# Knobber_Topsheet.net
KiCad netlist of a schematic drawn in Altium Designer
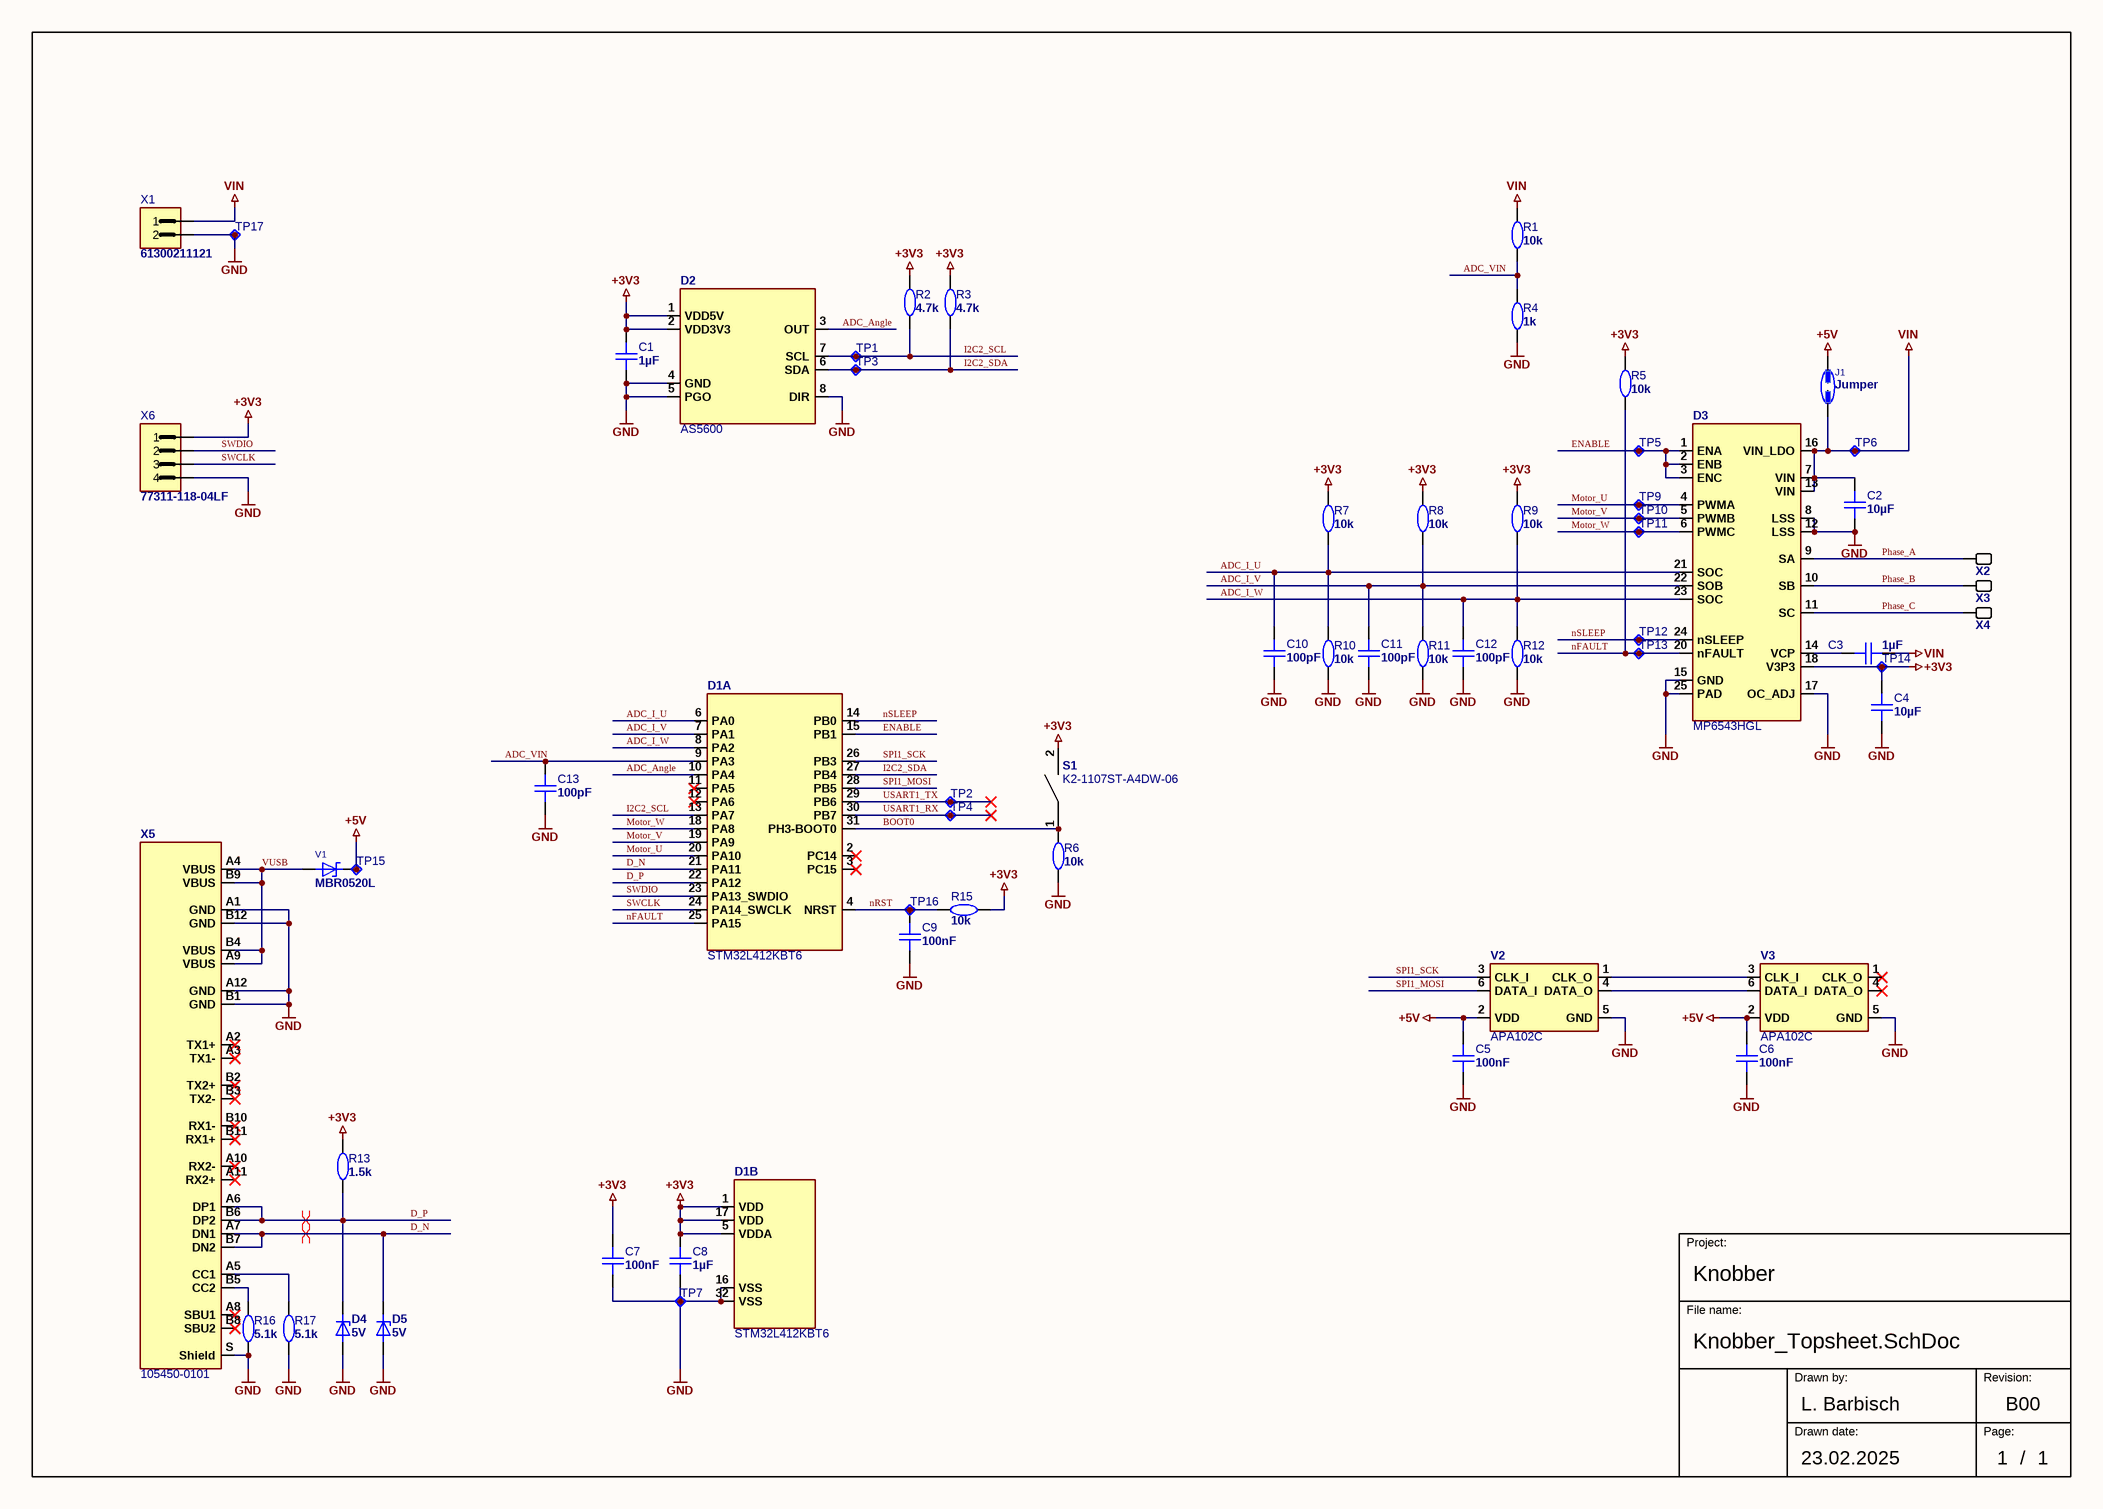
[diagram p0: Knobber_Topsheet.SchDoc]

(export (version "E")
  (design (tool "Eeschema 10.0.6"))
  (components
    (comp (ref "C1")
      (value "1µF")
      (footprint "C-0603_1608_095_L_RF")
      (description "Cap Cer SMD 1u 16V 10% 0603 X7R")
      (fields
        (field (name "MANUFACTURER PART NUMBER") "0603YC105KAT2A")
        (field (name "MANUFACTURER") "AVX")
        (field (name "USER") "epph")
      )
      (libsource (lib "GPV Switzerland SA") (part "CAP"))
    )
    (comp (ref "C2")
      (value "10µF")
      (footprint "C-1210_3225_230_L_RF")
      (description "CAP CER 10uF 50V X7S 1210")
      (fields
        (field (name "MANUFACTURER") "TDK")
        (field (name "MANUFACTURER PART NUMBER") "C3225X7S1H106K250AE")
        (field (name "USER") "zupa")
      )
      (libsource (lib "GPV Switzerland SA") (part "CAP"))
    )
    (comp (ref "C3")
      (value "1µF")
      (footprint "C-0603_1608_095_L_RF")
      (description "Cap Cer SMD 1u 16V 10% 0603 X7R")
      (fields
        (field (name "MANUFACTURER PART NUMBER") "0603YC105KAT2A")
        (field (name "MANUFACTURER") "AVX")
        (field (name "USER") "epph")
      )
      (libsource (lib "GPV Switzerland SA") (part "CAP"))
    )
    (comp (ref "C4")
      (value "10µF")
      (footprint "C-0805_2012_145_L_RF")
      (description "Cap Cer SMD 10u 16V 10% 0805 X5R")
      (fields
        (field (name "MANUFACTURER PART NUMBER") "0805YD106KAT2A")
        (field (name "MANUFACTURER") "AVX")
        (field (name "USER") "zupa")
      )
      (libsource (lib "GPV Switzerland SA") (part "CAP"))
    )
    (comp (ref "C5")
      (value "100nF")
      (footprint "C-0603_1608_095_L_RF")
      (description "Cap Cer SMD 100n 100V 10% 0603 X7R")
      (fields
        (field (name "MANUFACTURER PART NUMBER") "GRM188R72A104KA35")
        (field (name "MANUFACTURER") "MURATA")
        (field (name "USER") "zupa")
      )
      (libsource (lib "GPV Switzerland SA") (part "CAP"))
    )
    (comp (ref "C6")
      (value "100nF")
      (footprint "C-0603_1608_095_L_RF")
      (description "Cap Cer SMD 100n 100V 10% 0603 X7R")
      (fields
        (field (name "MANUFACTURER PART NUMBER") "GRM188R72A104KA35")
        (field (name "MANUFACTURER") "MURATA")
        (field (name "USER") "zupa")
      )
      (libsource (lib "GPV Switzerland SA") (part "CAP"))
    )
    (comp (ref "C7")
      (value "100nF")
      (footprint "C-0603_1608_095_L_RF")
      (description "Cap Cer SMD 100n 100V 10% 0603 X7R")
      (fields
        (field (name "MANUFACTURER PART NUMBER") "GRM188R72A104KA35")
        (field (name "MANUFACTURER") "MURATA")
        (field (name "USER") "zupa")
      )
      (libsource (lib "GPV Switzerland SA") (part "CAP"))
    )
    (comp (ref "C8")
      (value "1µF")
      (footprint "C-0603_1608_095_L_RF")
      (description "Cap Cer SMD 1u 16V 10% 0603 X7R")
      (fields
        (field (name "MANUFACTURER PART NUMBER") "0603YC105KAT2A")
        (field (name "MANUFACTURER") "AVX")
        (field (name "USER") "epph")
      )
      (libsource (lib "GPV Switzerland SA") (part "CAP"))
    )
    (comp (ref "C9")
      (value "100nF")
      (footprint "C-0603_1608_095_L_RF")
      (description "Cap Cer SMD 100n 100V 10% 0603 X7R")
      (fields
        (field (name "MANUFACTURER PART NUMBER") "GRM188R72A104KA35")
        (field (name "MANUFACTURER") "MURATA")
        (field (name "USER") "zupa")
      )
      (libsource (lib "GPV Switzerland SA") (part "CAP"))
    )
    (comp (ref "C10")
      (value "100pF")
      (footprint "C-0603_1608_095_L_RF")
      (description "Cap Cer SMD 100p 50V 5% 0603 C0G")
      (fields
        (field (name "MANUFACTURER PART NUMBER") "CC0603J*NPO9BN101")
        (field (name "MANUFACTURER") "YAGEO")
        (field (name "USER") "zupa")
      )
      (libsource (lib "GPV Switzerland SA") (part "CAP"))
    )
    (comp (ref "C11")
      (value "100pF")
      (footprint "C-0603_1608_095_L_RF")
      (description "Cap Cer SMD 100p 50V 5% 0603 C0G")
      (fields
        (field (name "MANUFACTURER PART NUMBER") "CC0603J*NPO9BN101")
        (field (name "MANUFACTURER") "YAGEO")
        (field (name "USER") "zupa")
      )
      (libsource (lib "GPV Switzerland SA") (part "CAP"))
    )
    (comp (ref "C12")
      (value "100pF")
      (footprint "C-0603_1608_095_L_RF")
      (description "Cap Cer SMD 100p 50V 5% 0603 C0G")
      (fields
        (field (name "MANUFACTURER PART NUMBER") "CC0603J*NPO9BN101")
        (field (name "MANUFACTURER") "YAGEO")
        (field (name "USER") "zupa")
      )
      (libsource (lib "GPV Switzerland SA") (part "CAP"))
    )
    (comp (ref "C13")
      (value "100pF")
      (footprint "C-0603_1608_095_L_RF")
      (description "Cap Cer SMD 100p 50V 5% 0603 C0G")
      (fields
        (field (name "MANUFACTURER PART NUMBER") "CC0603J*NPO9BN101")
        (field (name "MANUFACTURER") "YAGEO")
        (field (name "USER") "zupa")
      )
      (libsource (lib "GPV Switzerland SA") (part "CAP"))
    )
    (comp (ref "D1")
      (value "STM32L412KBT6")
      (footprint "LQFP32_N_RF")
      (description "IC MCU STM32")
      (fields (field (name "MANUFACTURER") "STM"))
      (libsource (lib "Global Library") (part "STM32L412KBT6"))
    )
    (comp (ref "D2")
      (value "AS5600")
      (footprint "SOIC8_N_RF")
      (description "IC Sensor Rotation Magnet 12bit")
      (fields (field (name "MANUFACTURER") "AMS"))
      (libsource (lib "Global Library") (part "AS5600"))
    )
    (comp (ref "D3")
      (value "MP6543HGL")
      (footprint "QFN24_5x7_N_RF")
      (description "Motor Driver 3-Phase 3-22V 2A")
      (fields
        (field (name "MANUFACTURER") "Monolithic Power Systems")
        (field (name "MANUFACTURER PART NUMBER") "MP6543HGL-A-P")
      )
      (libsource (lib "Global Library") (part "MP6543HGL-A-P"))
    )
    (comp (ref "D4")
      (value "5V")
      (footprint "SOD-923_N_RF")
      (description "Diode ESD 5V")
      (fields
        (field (name "MANUFACTURER") "Onsemi")
        (field (name "MANUFACTURER PART NUMBER") "ESD9101P2T5G")
        (field (name "PART_VALIDATED") "Yes ¦ No")
        (field (name "FOOTPRINT_VALIDATED") "Yes ¦ No")
      )
      (libsource (lib "Global Library") (part "ESD9101"))
    )
    (comp (ref "D5")
      (value "5V")
      (footprint "SOD-923_N_RF")
      (description "Diode ESD 5V")
      (fields
        (field (name "MANUFACTURER") "Onsemi")
        (field (name "MANUFACTURER PART NUMBER") "ESD9101P2T5G")
        (field (name "PART_VALIDATED") "Yes ¦ No")
        (field (name "FOOTPRINT_VALIDATED") "Yes ¦ No")
      )
      (libsource (lib "Global Library") (part "ESD9101"))
    )
    (comp (ref "J1")
      (value "Jumper")
      (footprint "J-1206_Solderjumper_2Pin")
      (description "Solder jumper 2Pin")
      (fields (field (name "USER") "epph"))
      (libsource (lib "GPV Switzerland SA") (part "Solder jumper 2Pin"))
    )
    (comp (ref "R1")
      (value "10k")
      (footprint "R-0603_1608_050_L_RF")
      (description "Res SMD 10k 1% 0.1W 0603")
      (fields
        (field (name "MANUFACTURER") "KOA")
        (field (name "MANUFACTURER PART NUMBER") "RK73H1JTTD1002F")
        (field (name "USER") "epph")
      )
      (libsource (lib "GPV Switzerland SA") (part "RES"))
    )
    (comp (ref "R2")
      (value "4.7k")
      (footprint "R-0603_1608_050_L_RF")
      (description "Res SMD 4k7 1% 0.1W 0603")
      (fields
        (field (name "MANUFACTURER PART NUMBER") "RC0603FR-074K7L")
        (field (name "MANUFACTURER") "YAGEO")
        (field (name "USER") "zupa")
      )
      (libsource (lib "GPV Switzerland SA") (part "RES"))
    )
    (comp (ref "R3")
      (value "4.7k")
      (footprint "R-0603_1608_050_L_RF")
      (description "Res SMD 4k7 1% 0.1W 0603")
      (fields
        (field (name "MANUFACTURER PART NUMBER") "RC0603FR-074K7L")
        (field (name "MANUFACTURER") "YAGEO")
        (field (name "USER") "zupa")
      )
      (libsource (lib "GPV Switzerland SA") (part "RES"))
    )
    (comp (ref "R4")
      (value "1k")
      (footprint "R-0603_1608_050_L_RF")
      (description "Res SMD 1k 1% 0.1W 0603")
      (fields
        (field (name "MANUFACTURER") "YAGEO")
        (field (name "MANUFACTURER PART NUMBER") "RC0603FR-071KL")
        (field (name "USER") "zupa")
      )
      (libsource (lib "GPV Switzerland SA") (part "RES"))
    )
    (comp (ref "R5")
      (value "10k")
      (footprint "R-0603_1608_050_L_RF")
      (description "Res SMD 10k 1% 0.1W 0603")
      (fields
        (field (name "MANUFACTURER") "KOA")
        (field (name "MANUFACTURER PART NUMBER") "RK73H1JTTD1002F")
        (field (name "USER") "epph")
      )
      (libsource (lib "GPV Switzerland SA") (part "RES"))
    )
    (comp (ref "R6")
      (value "10k")
      (footprint "R-0603_1608_050_L_RF")
      (description "Res SMD 10k 1% 0.1W 0603")
      (fields
        (field (name "MANUFACTURER") "KOA")
        (field (name "MANUFACTURER PART NUMBER") "RK73H1JTTD1002F")
        (field (name "USER") "epph")
      )
      (libsource (lib "GPV Switzerland SA") (part "RES"))
    )
    (comp (ref "R7")
      (value "10k")
      (footprint "R-0603_1608_050_L_RF")
      (description "Res SMD 10k 1% 0.1W 0603")
      (fields
        (field (name "MANUFACTURER") "KOA")
        (field (name "MANUFACTURER PART NUMBER") "RK73H1JTTD1002F")
        (field (name "USER") "epph")
      )
      (libsource (lib "GPV Switzerland SA") (part "RES"))
    )
    (comp (ref "R8")
      (value "10k")
      (footprint "R-0603_1608_050_L_RF")
      (description "Res SMD 10k 1% 0.1W 0603")
      (fields
        (field (name "MANUFACTURER") "KOA")
        (field (name "MANUFACTURER PART NUMBER") "RK73H1JTTD1002F")
        (field (name "USER") "epph")
      )
      (libsource (lib "GPV Switzerland SA") (part "RES"))
    )
    (comp (ref "R9")
      (value "10k")
      (footprint "R-0603_1608_050_L_RF")
      (description "Res SMD 10k 1% 0.1W 0603")
      (fields
        (field (name "MANUFACTURER") "KOA")
        (field (name "MANUFACTURER PART NUMBER") "RK73H1JTTD1002F")
        (field (name "USER") "epph")
      )
      (libsource (lib "GPV Switzerland SA") (part "RES"))
    )
    (comp (ref "R10")
      (value "10k")
      (footprint "R-0603_1608_050_L_RF")
      (description "Res SMD 10k 1% 0.1W 0603")
      (fields
        (field (name "MANUFACTURER") "KOA")
        (field (name "MANUFACTURER PART NUMBER") "RK73H1JTTD1002F")
        (field (name "USER") "epph")
      )
      (libsource (lib "GPV Switzerland SA") (part "RES"))
    )
    (comp (ref "R11")
      (value "10k")
      (footprint "R-0603_1608_050_L_RF")
      (description "Res SMD 10k 1% 0.1W 0603")
      (fields
        (field (name "MANUFACTURER") "KOA")
        (field (name "MANUFACTURER PART NUMBER") "RK73H1JTTD1002F")
        (field (name "USER") "epph")
      )
      (libsource (lib "GPV Switzerland SA") (part "RES"))
    )
    (comp (ref "R12")
      (value "10k")
      (footprint "R-0603_1608_050_L_RF")
      (description "Res SMD 10k 1% 0.1W 0603")
      (fields
        (field (name "MANUFACTURER") "KOA")
        (field (name "MANUFACTURER PART NUMBER") "RK73H1JTTD1002F")
        (field (name "USER") "epph")
      )
      (libsource (lib "GPV Switzerland SA") (part "RES"))
    )
    (comp (ref "R13")
      (value "1.5k")
      (footprint "R-0603_1608_050_L_RF")
      (description "Res SMD 1k5 1% 0.1W 0603")
      (fields
        (field (name "MANUFACTURER") "YAGEO")
        (field (name "MANUFACTURER PART NUMBER") "RC0603FR-071K5L")
        (field (name "USER") "epph")
      )
      (libsource (lib "GPV Switzerland SA") (part "RES"))
    )
    (comp (ref "R15")
      (value "10k")
      (footprint "R-0603_1608_050_L_RF")
      (description "Res SMD 10k 1% 0.1W 0603")
      (fields
        (field (name "MANUFACTURER") "KOA")
        (field (name "MANUFACTURER PART NUMBER") "RK73H1JTTD1002F")
        (field (name "USER") "epph")
      )
      (libsource (lib "GPV Switzerland SA") (part "RES"))
    )
    (comp (ref "R16")
      (value "5.1k")
      (footprint "R-0603_1608_050_L_RF")
      (description "Res SMD 5k1 1% 0.1W 0603")
      (fields
        (field (name "MANUFACTURER PART NUMBER") "RC0603FR-075K1L")
        (field (name "MANUFACTURER") "YAGEO")
        (field (name "USER") "napa")
      )
      (libsource (lib "GPV Switzerland SA") (part "RES"))
    )
    (comp (ref "R17")
      (value "5.1k")
      (footprint "R-0603_1608_050_L_RF")
      (description "Res SMD 5k1 1% 0.1W 0603")
      (fields
        (field (name "MANUFACTURER PART NUMBER") "RC0603FR-075K1L")
        (field (name "MANUFACTURER") "YAGEO")
        (field (name "USER") "napa")
      )
      (libsource (lib "GPV Switzerland SA") (part "RES"))
    )
    (comp (ref "S1")
      (value "K2-1107ST-A4DW-06")
      (footprint "K2-1107ST-A4DW-06")
      (description "BUTTON tactile 12V 50mA")
      (fields
        (field (name "MANUFACTURER") "HROparts")
        (field (name "MANUFACTURER PART NUMBER") "K2-1107ST-A4DW-06 (C118141)")
      )
      (libsource (lib "Global Library") (part "K2-1107ST-A4DW-06"))
    )
    (comp (ref "TP1")
      (value "TestPoint 0.8mm")
      (footprint "TP_0.8mm")
      (fields (field (name "USER") "zupa"))
      (libsource (lib "GPV Switzerland SA") (part "Testpoint"))
    )
    (comp (ref "TP2")
      (value "TestPoint 0.8mm")
      (footprint "TP_0.8mm")
      (fields (field (name "USER") "zupa"))
      (libsource (lib "GPV Switzerland SA") (part "Testpoint"))
    )
    (comp (ref "TP3")
      (value "TestPoint 0.8mm")
      (footprint "TP_0.8mm")
      (fields (field (name "USER") "zupa"))
      (libsource (lib "GPV Switzerland SA") (part "Testpoint"))
    )
    (comp (ref "TP4")
      (value "TestPoint 0.8mm")
      (footprint "TP_0.8mm")
      (fields (field (name "USER") "zupa"))
      (libsource (lib "GPV Switzerland SA") (part "Testpoint"))
    )
    (comp (ref "TP5")
      (value "TestPoint 0.8mm")
      (footprint "TP_0.8mm")
      (fields (field (name "USER") "zupa"))
      (libsource (lib "GPV Switzerland SA") (part "Testpoint"))
    )
    (comp (ref "TP6")
      (value "TestPoint 0.8mm")
      (footprint "TP_0.8mm")
      (fields (field (name "USER") "zupa"))
      (libsource (lib "GPV Switzerland SA") (part "Testpoint"))
    )
    (comp (ref "TP7")
      (value "TestPoint 0.8mm")
      (footprint "TP_0.8mm")
      (fields (field (name "USER") "zupa"))
      (libsource (lib "GPV Switzerland SA") (part "Testpoint"))
    )
    (comp (ref "TP9")
      (value "TestPoint 0.8mm")
      (footprint "TP_0.8mm")
      (fields (field (name "USER") "zupa"))
      (libsource (lib "GPV Switzerland SA") (part "Testpoint"))
    )
    (comp (ref "TP10")
      (value "TestPoint 0.8mm")
      (footprint "TP_0.8mm")
      (fields (field (name "USER") "zupa"))
      (libsource (lib "GPV Switzerland SA") (part "Testpoint"))
    )
    (comp (ref "TP11")
      (value "TestPoint 0.8mm")
      (footprint "TP_0.8mm")
      (fields (field (name "USER") "zupa"))
      (libsource (lib "GPV Switzerland SA") (part "Testpoint"))
    )
    (comp (ref "TP12")
      (value "TestPoint 0.8mm")
      (footprint "TP_0.8mm")
      (fields (field (name "USER") "zupa"))
      (libsource (lib "GPV Switzerland SA") (part "Testpoint"))
    )
    (comp (ref "TP13")
      (value "TestPoint 0.8mm")
      (footprint "TP_0.8mm")
      (fields (field (name "USER") "zupa"))
      (libsource (lib "GPV Switzerland SA") (part "Testpoint"))
    )
    (comp (ref "TP14")
      (value "TestPoint 0.8mm")
      (footprint "TP_0.8mm")
      (fields (field (name "USER") "zupa"))
      (libsource (lib "GPV Switzerland SA") (part "Testpoint"))
    )
    (comp (ref "TP15")
      (value "TestPoint 0.8mm")
      (footprint "TP_0.8mm")
      (fields (field (name "USER") "zupa"))
      (libsource (lib "GPV Switzerland SA") (part "Testpoint"))
    )
    (comp (ref "TP16")
      (value "TestPoint 0.8mm")
      (footprint "TP_0.8mm")
      (fields (field (name "USER") "zupa"))
      (libsource (lib "GPV Switzerland SA") (part "Testpoint"))
    )
    (comp (ref "TP17")
      (value "TestPoint 0.8mm")
      (footprint "TP_0.8mm")
      (fields (field (name "USER") "zupa"))
      (libsource (lib "GPV Switzerland SA") (part "Testpoint"))
    )
    (comp (ref "V1")
      (value "MBR0520L")
      (footprint "SOD123_L_RF")
      (description "Diode Schottky 20V 0.5A SOD123")
      (fields
        (field (name "MANUFACTURER") "ONSemi")
        (field (name "MANUFACTURER PART NUMBER") "MBR0520LT1G")
        (field (name "USER") "epph")
      )
      (libsource (lib "GPV Switzerland SA") (part "SCHOTTKY"))
    )
    (comp (ref "V2")
      (value "APA102C")
      (footprint "V_2020_P6_N_RF")
      (description "RGB LED SPI Interface")
      (fields
        (field (name "MANUFACTURER") "APA Electronic CO")
        (field (name "MANUFACTURER PART NUMBER") "APA-102-2020-256-8A")
      )
      (libsource (lib "Global Library") (part "APA102C"))
    )
    (comp (ref "V3")
      (value "APA102C")
      (footprint "V_2020_P6_N_RF")
      (description "RGB LED SPI Interface")
      (fields
        (field (name "MANUFACTURER") "APA Electronic CO")
        (field (name "MANUFACTURER PART NUMBER") "APA-102-2020-256-8A")
      )
      (libsource (lib "Global Library") (part "APA102C"))
    )
    (comp (ref "X1")
      (value "61300211121")
      (footprint "X-0508X0254_R_WE_61300211121")
      (description "CONN HEADER 2POS 1ROW THT 2.54MM WE 61300211121")
      (fields
        (field (name "MANUFACTURER") "WE")
        (field (name "Comment") "CONN HEADER 2POS 1ROW THT 2.54MM")
        (field (name "USER") "balu")
      )
      (libsource (lib "GPV Switzerland SA") (part "Connector-2P"))
    )
    (comp (ref "X2")
      (value "~")
      (footprint "Lötpad_2x3")
      (description "Solderpad 2mm x 3mm")
      (libsource (lib "Global Library") (part "Lötpad_2mmx3mm"))
    )
    (comp (ref "X3")
      (value "~")
      (footprint "Lötpad_2x3")
      (description "Solderpad 2mm x 3mm")
      (libsource (lib "Global Library") (part "Lötpad_2mmx3mm"))
    )
    (comp (ref "X4")
      (value "~")
      (footprint "Lötpad_2x3")
      (description "Solderpad 2mm x 3mm")
      (libsource (lib "Global Library") (part "Lötpad_2mmx3mm"))
    )
    (comp (ref "X5")
      (value "105450-0101")
      (footprint "105450-0101")
      (description "CONN USB-C 16pin")
      (fields (field (name "MANUFACTURER") "Molex"))
      (libsource (lib "Global Library") (part "105450-0101"))
    )
    (comp (ref "X6")
      (value "77311-118-04LF")
      (footprint "X-0101X0025_R_FCI_77311-118-04LF")
      (description "CONN HEADER 4POS 1ROW THT 2.54MM FCI 77311-118-04LF")
      (fields
        (field (name "MANUFACTURER") "FCI")
        (field (name "Comment") "CONN HEADER 4POS 1ROW THT 2.54MM")
        (field (name "USER") "zupa")
      )
      (libsource (lib "GPV Switzerland SA") (part "Connector-4P"))
    )
  )
  (nets
    (net (code "1") (name "+3V3") (class "Default")
      (node (ref "C1") (pin "2") (pinfunction "2_2") (pintype "passive"))
      (node (ref "C4") (pin "2") (pinfunction "2_2") (pintype "passive"))
      (node (ref "C7") (pin "2") (pinfunction "2_2") (pintype "passive"))
      (node (ref "C8") (pin "2") (pinfunction "2_2") (pintype "passive"))
      (node (ref "D1") (pin "1") (pinfunction "VDD_1") (pintype "passive"))
      (node (ref "D1") (pin "17") (pinfunction "VDD_17") (pintype "passive"))
      (node (ref "D1") (pin "5") (pinfunction "VDDA_5") (pintype "passive"))
      (node (ref "D2") (pin "1") (pinfunction "VDD5V_1") (pintype "passive"))
      (node (ref "D2") (pin "2") (pinfunction "VDD3V3_2") (pintype "passive"))
      (node (ref "D3") (pin "18") (pinfunction "V3P3_18") (pintype "passive"))
      (node (ref "R13") (pin "2") (pinfunction "2_2") (pintype "passive"))
      (node (ref "R15") (pin "1") (pinfunction "1_1") (pintype "passive"))
      (node (ref "R2") (pin "2") (pinfunction "2_2") (pintype "passive"))
      (node (ref "R3") (pin "2") (pinfunction "2_2") (pintype "passive"))
      (node (ref "R5") (pin "2") (pinfunction "2_2") (pintype "passive"))
      (node (ref "R7") (pin "2") (pinfunction "2_2") (pintype "passive"))
      (node (ref "R8") (pin "2") (pinfunction "2_2") (pintype "passive"))
      (node (ref "R9") (pin "2") (pinfunction "2_2") (pintype "passive"))
      (node (ref "S1") (pin "2") (pintype "passive"))
      (node (ref "TP14") (pin "1") (pinfunction "1_1") (pintype "passive"))
      (node (ref "X6") (pin "1") (pinfunction "1_1") (pintype "passive"))
    )
    (net (code "2") (name "+5V") (class "Default")
      (node (ref "C5") (pin "2") (pinfunction "2_2") (pintype "passive"))
      (node (ref "C6") (pin "2") (pinfunction "2_2") (pintype "passive"))
      (node (ref "J1") (pin "2") (pinfunction "2_2") (pintype "passive"))
      (node (ref "TP15") (pin "1") (pinfunction "1_1") (pintype "passive"))
      (node (ref "V1") (pin "2") (pinfunction "2_2") (pintype "passive"))
      (node (ref "V2") (pin "2") (pinfunction "VDD_2") (pintype "passive"))
      (node (ref "V3") (pin "2") (pinfunction "VDD_2") (pintype "passive"))
    )
    (net (code "3") (name "/ADC_Angle") (class "Default")
      (node (ref "D1") (pin "10") (pinfunction "PA4_10") (pintype "passive"))
      (node (ref "D2") (pin "3") (pinfunction "OUT_3") (pintype "passive"))
    )
    (net (code "4") (name "/ADC_I_U") (class "Default")
      (node (ref "C10") (pin "2") (pinfunction "2_2") (pintype "passive"))
      (node (ref "D1") (pin "6") (pinfunction "PA0_6") (pintype "passive"))
      (node (ref "D3") (pin "21") (pinfunction "SOC_21") (pintype "passive"))
      (node (ref "R10") (pin "2") (pinfunction "2_2") (pintype "passive"))
      (node (ref "R7") (pin "1") (pinfunction "1_1") (pintype "passive"))
    )
    (net (code "5") (name "/ADC_I_V") (class "Default")
      (node (ref "C11") (pin "2") (pinfunction "2_2") (pintype "passive"))
      (node (ref "D1") (pin "7") (pinfunction "PA1_7") (pintype "passive"))
      (node (ref "D3") (pin "22") (pinfunction "SOB_22") (pintype "passive"))
      (node (ref "R11") (pin "2") (pinfunction "2_2") (pintype "passive"))
      (node (ref "R8") (pin "1") (pinfunction "1_1") (pintype "passive"))
    )
    (net (code "6") (name "/ADC_I_W") (class "Default")
      (node (ref "C12") (pin "2") (pinfunction "2_2") (pintype "passive"))
      (node (ref "D1") (pin "8") (pinfunction "PA2_8") (pintype "passive"))
      (node (ref "D3") (pin "23") (pinfunction "SOC_23") (pintype "passive"))
      (node (ref "R12") (pin "2") (pinfunction "2_2") (pintype "passive"))
      (node (ref "R9") (pin "1") (pinfunction "1_1") (pintype "passive"))
    )
    (net (code "7") (name "/ADC_VIN") (class "Default")
      (node (ref "C13") (pin "2") (pinfunction "2_2") (pintype "passive"))
      (node (ref "D1") (pin "9") (pinfunction "PA3_9") (pintype "passive"))
      (node (ref "R1") (pin "1") (pinfunction "1_1") (pintype "passive"))
      (node (ref "R4") (pin "2") (pinfunction "2_2") (pintype "passive"))
    )
    (net (code "8") (name "/BOOT0") (class "Default")
      (node (ref "D1") (pin "31") (pinfunction "PH3-BOOT0_31") (pintype "passive"))
      (node (ref "R6") (pin "2") (pinfunction "2_2") (pintype "passive"))
      (node (ref "S1") (pin "1") (pintype "passive"))
    )
    (net (code "9") (name "/D_N") (class "Default")
      (node (ref "D1") (pin "21") (pinfunction "PA11_21") (pintype "passive"))
      (node (ref "D5") (pin "2") (pinfunction "2_2") (pintype "passive"))
      (node (ref "X5") (pin "A7") (pinfunction "DN1_A7") (pintype "passive"))
      (node (ref "X5") (pin "B7") (pinfunction "DN2_B7") (pintype "passive"))
    )
    (net (code "10") (name "/D_P") (class "Default")
      (node (ref "D1") (pin "22") (pinfunction "PA12_22") (pintype "passive"))
      (node (ref "D4") (pin "2") (pinfunction "2_2") (pintype "passive"))
      (node (ref "R13") (pin "1") (pinfunction "1_1") (pintype "passive"))
      (node (ref "X5") (pin "A6") (pinfunction "DP1_A6") (pintype "passive"))
      (node (ref "X5") (pin "B6") (pinfunction "DP2_B6") (pintype "passive"))
    )
    (net (code "11") (name "/ENABLE") (class "Default")
      (node (ref "D1") (pin "15") (pinfunction "PB1_15") (pintype "passive"))
      (node (ref "D3") (pin "1") (pinfunction "ENA_1") (pintype "passive"))
      (node (ref "D3") (pin "2") (pinfunction "ENB_2") (pintype "passive"))
      (node (ref "D3") (pin "3") (pinfunction "ENC_3") (pintype "passive"))
      (node (ref "TP5") (pin "1") (pinfunction "1_1") (pintype "passive"))
    )
    (net (code "12") (name "/I2C2_SCL") (class "Default")
      (node (ref "D1") (pin "13") (pinfunction "PA7_13") (pintype "passive"))
      (node (ref "D2") (pin "7") (pinfunction "SCL_7") (pintype "passive"))
      (node (ref "R2") (pin "1") (pinfunction "1_1") (pintype "passive"))
      (node (ref "TP1") (pin "1") (pinfunction "1_1") (pintype "passive"))
    )
    (net (code "13") (name "/I2C2_SDA") (class "Default")
      (node (ref "D1") (pin "27") (pinfunction "PB4_27") (pintype "passive"))
      (node (ref "D2") (pin "6") (pinfunction "SDA_6") (pintype "passive"))
      (node (ref "R3") (pin "1") (pinfunction "1_1") (pintype "passive"))
      (node (ref "TP3") (pin "1") (pinfunction "1_1") (pintype "passive"))
    )
    (net (code "14") (name "/Motor_U") (class "Default")
      (node (ref "D1") (pin "20") (pinfunction "PA10_20") (pintype "passive"))
      (node (ref "D3") (pin "4") (pinfunction "PWMA_4") (pintype "passive"))
      (node (ref "TP9") (pin "1") (pinfunction "1_1") (pintype "passive"))
    )
    (net (code "15") (name "/Motor_V") (class "Default")
      (node (ref "D1") (pin "19") (pinfunction "PA9_19") (pintype "passive"))
      (node (ref "D3") (pin "5") (pinfunction "PWMB_5") (pintype "passive"))
      (node (ref "TP10") (pin "1") (pinfunction "1_1") (pintype "passive"))
    )
    (net (code "16") (name "/Motor_W") (class "Default")
      (node (ref "D1") (pin "18") (pinfunction "PA8_18") (pintype "passive"))
      (node (ref "D3") (pin "6") (pinfunction "PWMC_6") (pintype "passive"))
      (node (ref "TP11") (pin "1") (pinfunction "1_1") (pintype "passive"))
    )
    (net (code "17") (name "/Phase_A") (class "Default")
      (node (ref "D3") (pin "9") (pinfunction "SA_9") (pintype "passive"))
      (node (ref "X2") (pin "1") (pintype "passive"))
    )
    (net (code "18") (name "/Phase_B") (class "Default")
      (node (ref "D3") (pin "10") (pinfunction "SB_10") (pintype "passive"))
      (node (ref "X3") (pin "1") (pintype "passive"))
    )
    (net (code "19") (name "/Phase_C") (class "Default")
      (node (ref "D3") (pin "11") (pinfunction "SC_11") (pintype "passive"))
      (node (ref "X4") (pin "1") (pintype "passive"))
    )
    (net (code "20") (name "/SPI1_MOSI") (class "Default")
      (node (ref "D1") (pin "28") (pinfunction "PB5_28") (pintype "passive"))
      (node (ref "V2") (pin "6") (pinfunction "DATA_I_6") (pintype "passive"))
    )
    (net (code "21") (name "/SPI1_SCK") (class "Default")
      (node (ref "D1") (pin "26") (pinfunction "PB3_26") (pintype "passive"))
      (node (ref "V2") (pin "3") (pinfunction "CLK_I_3") (pintype "passive"))
    )
    (net (code "22") (name "/SWCLK") (class "Default")
      (node (ref "D1") (pin "24") (pinfunction "PA14_SWCLK_24") (pintype "passive"))
      (node (ref "X6") (pin "3") (pinfunction "3_3") (pintype "passive"))
    )
    (net (code "23") (name "/SWDIO") (class "Default")
      (node (ref "D1") (pin "23") (pinfunction "PA13_SWDIO_23") (pintype "passive"))
      (node (ref "X6") (pin "2") (pinfunction "2_2") (pintype "passive"))
    )
    (net (code "24") (name "/USART1_RX") (class "Default")
      (node (ref "D1") (pin "30") (pinfunction "PB7_30") (pintype "passive"))
      (node (ref "TP4") (pin "1") (pinfunction "1_1") (pintype "passive"))
    )
    (net (code "25") (name "/USART1_TX") (class "Default")
      (node (ref "D1") (pin "29") (pinfunction "PB6_29") (pintype "passive"))
      (node (ref "TP2") (pin "1") (pinfunction "1_1") (pintype "passive"))
    )
    (net (code "26") (name "/VUSB") (class "Default")
      (node (ref "V1") (pin "1") (pinfunction "1_1") (pintype "passive"))
      (node (ref "X5") (pin "A4") (pinfunction "VBUS_A4") (pintype "passive"))
      (node (ref "X5") (pin "A9") (pinfunction "VBUS_A9") (pintype "passive"))
      (node (ref "X5") (pin "B4") (pinfunction "VBUS_B4") (pintype "passive"))
      (node (ref "X5") (pin "B9") (pinfunction "VBUS_B9") (pintype "passive"))
    )
    (net (code "27") (name "/nFAULT") (class "Default")
      (node (ref "D1") (pin "25") (pinfunction "PA15_25") (pintype "passive"))
      (node (ref "D3") (pin "20") (pinfunction "nFAULT_20") (pintype "passive"))
      (node (ref "R5") (pin "1") (pinfunction "1_1") (pintype "passive"))
      (node (ref "TP13") (pin "1") (pinfunction "1_1") (pintype "passive"))
    )
    (net (code "28") (name "/nRST") (class "Default")
      (node (ref "C9") (pin "2") (pinfunction "2_2") (pintype "passive"))
      (node (ref "D1") (pin "4") (pinfunction "NRST_4") (pintype "passive"))
      (node (ref "R15") (pin "2") (pinfunction "2_2") (pintype "passive"))
      (node (ref "TP16") (pin "1") (pinfunction "1_1") (pintype "passive"))
    )
    (net (code "29") (name "/nSLEEP") (class "Default")
      (node (ref "D1") (pin "14") (pinfunction "PB0_14") (pintype "passive"))
      (node (ref "D3") (pin "24") (pinfunction "nSLEEP_24") (pintype "passive"))
      (node (ref "TP12") (pin "1") (pinfunction "1_1") (pintype "passive"))
    )
    (net (code "30") (name "GND") (class "Default")
      (node (ref "C1") (pin "1") (pinfunction "1_1") (pintype "passive"))
      (node (ref "C10") (pin "1") (pinfunction "1_1") (pintype "passive"))
      (node (ref "C11") (pin "1") (pinfunction "1_1") (pintype "passive"))
      (node (ref "C12") (pin "1") (pinfunction "1_1") (pintype "passive"))
      (node (ref "C13") (pin "1") (pinfunction "1_1") (pintype "passive"))
      (node (ref "C2") (pin "1") (pinfunction "1_1") (pintype "passive"))
      (node (ref "C4") (pin "1") (pinfunction "1_1") (pintype "passive"))
      (node (ref "C5") (pin "1") (pinfunction "1_1") (pintype "passive"))
      (node (ref "C6") (pin "1") (pinfunction "1_1") (pintype "passive"))
      (node (ref "C7") (pin "1") (pinfunction "1_1") (pintype "passive"))
      (node (ref "C8") (pin "1") (pinfunction "1_1") (pintype "passive"))
      (node (ref "C9") (pin "1") (pinfunction "1_1") (pintype "passive"))
      (node (ref "D1") (pin "16") (pinfunction "VSS_16") (pintype "passive"))
      (node (ref "D1") (pin "32") (pinfunction "VSS_32") (pintype "passive"))
      (node (ref "D2") (pin "4") (pinfunction "GND_4") (pintype "passive"))
      (node (ref "D2") (pin "5") (pinfunction "PGO_5") (pintype "passive"))
      (node (ref "D2") (pin "8") (pinfunction "DIR_8") (pintype "passive"))
      (node (ref "D3") (pin "12") (pinfunction "LSS_12") (pintype "passive"))
      (node (ref "D3") (pin "15") (pinfunction "GND_15") (pintype "passive"))
      (node (ref "D3") (pin "17") (pinfunction "OC_ADJ_17") (pintype "passive"))
      (node (ref "D3") (pin "25") (pinfunction "PAD_25") (pintype "passive"))
      (node (ref "D3") (pin "8") (pinfunction "LSS_8") (pintype "passive"))
      (node (ref "D4") (pin "1") (pinfunction "1_1") (pintype "passive"))
      (node (ref "D5") (pin "1") (pinfunction "1_1") (pintype "passive"))
      (node (ref "R10") (pin "1") (pinfunction "1_1") (pintype "passive"))
      (node (ref "R11") (pin "1") (pinfunction "1_1") (pintype "passive"))
      (node (ref "R12") (pin "1") (pinfunction "1_1") (pintype "passive"))
      (node (ref "R16") (pin "1") (pinfunction "1_1") (pintype "passive"))
      (node (ref "R17") (pin "1") (pinfunction "1_1") (pintype "passive"))
      (node (ref "R4") (pin "1") (pinfunction "1_1") (pintype "passive"))
      (node (ref "R6") (pin "1") (pinfunction "1_1") (pintype "passive"))
      (node (ref "TP17") (pin "1") (pinfunction "1_1") (pintype "passive"))
      (node (ref "TP7") (pin "1") (pinfunction "1_1") (pintype "passive"))
      (node (ref "V2") (pin "5") (pinfunction "GND_5") (pintype "passive"))
      (node (ref "V3") (pin "5") (pinfunction "GND_5") (pintype "passive"))
      (node (ref "X1") (pin "2") (pinfunction "2_2") (pintype "passive"))
      (node (ref "X5") (pin "A1") (pinfunction "GND_A1") (pintype "passive"))
      (node (ref "X5") (pin "A12") (pinfunction "GND_A12") (pintype "passive"))
      (node (ref "X5") (pin "B1") (pinfunction "GND_B1") (pintype "passive"))
      (node (ref "X5") (pin "B12") (pinfunction "GND_B12") (pintype "passive"))
      (node (ref "X5") (pin "S") (pinfunction "Shield_S") (pintype "passive"))
      (node (ref "X6") (pin "4") (pinfunction "4_4") (pintype "passive"))
    )
    (net (code "31") (name "Net-(D3-VCP)") (class "Default")
      (node (ref "C3") (pin "1") (pinfunction "1_1") (pintype "passive"))
      (node (ref "D3") (pin "14") (pinfunction "VCP_14") (pintype "passive"))
    )
    (net (code "32") (name "Net-(V2-CLK_O)") (class "Default")
      (node (ref "V2") (pin "1") (pinfunction "CLK_O_1") (pintype "passive"))
      (node (ref "V3") (pin "3") (pinfunction "CLK_I_3") (pintype "passive"))
    )
    (net (code "33") (name "Net-(V2-DATA_O)") (class "Default")
      (node (ref "V2") (pin "4") (pinfunction "DATA_O_4") (pintype "passive"))
      (node (ref "V3") (pin "6") (pinfunction "DATA_I_6") (pintype "passive"))
    )
    (net (code "34") (name "Net-(X5-CC1)") (class "Default")
      (node (ref "R17") (pin "2") (pinfunction "2_2") (pintype "passive"))
      (node (ref "X5") (pin "A5") (pinfunction "CC1_A5") (pintype "passive"))
    )
    (net (code "35") (name "Net-(X5-CC2)") (class "Default")
      (node (ref "R16") (pin "2") (pinfunction "2_2") (pintype "passive"))
      (node (ref "X5") (pin "B5") (pinfunction "CC2_B5") (pintype "passive"))
    )
    (net (code "36") (name "VIN") (class "Default")
      (node (ref "C2") (pin "2") (pinfunction "2_2") (pintype "passive"))
      (node (ref "C3") (pin "2") (pinfunction "2_2") (pintype "passive"))
      (node (ref "D3") (pin "13") (pinfunction "VIN_13") (pintype "passive"))
      (node (ref "D3") (pin "16") (pinfunction "VIN_LDO_16") (pintype "passive"))
      (node (ref "D3") (pin "7") (pinfunction "VIN_7") (pintype "passive"))
      (node (ref "J1") (pin "1") (pinfunction "1_1") (pintype "passive"))
      (node (ref "R1") (pin "2") (pinfunction "2_2") (pintype "passive"))
      (node (ref "TP6") (pin "1") (pinfunction "1_1") (pintype "passive"))
      (node (ref "X1") (pin "1") (pinfunction "1_1") (pintype "passive"))
    )
    (net (code "37") (name "unconnected-(D1A-PA5-Pad11)") (class "Default")
      (node (ref "D1") (pin "11") (pinfunction "PA5_11") (pintype "passive+no_connect"))
    )
    (net (code "38") (name "unconnected-(D1A-PA6-Pad12)") (class "Default")
      (node (ref "D1") (pin "12") (pinfunction "PA6_12") (pintype "passive+no_connect"))
    )
    (net (code "39") (name "unconnected-(D1A-PC14-Pad2)") (class "Default")
      (node (ref "D1") (pin "2") (pinfunction "PC14_2") (pintype "passive+no_connect"))
    )
    (net (code "40") (name "unconnected-(D1A-PC15-Pad3)") (class "Default")
      (node (ref "D1") (pin "3") (pinfunction "PC15_3") (pintype "passive+no_connect"))
    )
    (net (code "41") (name "unconnected-(V3-CLK_O-Pad1)") (class "Default")
      (node (ref "V3") (pin "1") (pinfunction "CLK_O_1") (pintype "passive+no_connect"))
    )
    (net (code "42") (name "unconnected-(V3-DATA_O-Pad4)") (class "Default")
      (node (ref "V3") (pin "4") (pinfunction "DATA_O_4") (pintype "passive+no_connect"))
    )
    (net (code "43") (name "unconnected-(X5-RX1+-PadB11)") (class "Default")
      (node (ref "X5") (pin "B11") (pinfunction "RX1+_B11") (pintype "passive+no_connect"))
    )
    (net (code "44") (name "unconnected-(X5-RX1--PadB10)") (class "Default")
      (node (ref "X5") (pin "B10") (pinfunction "RX1-_B10") (pintype "passive+no_connect"))
    )
    (net (code "45") (name "unconnected-(X5-RX2+-PadA11)") (class "Default")
      (node (ref "X5") (pin "A11") (pinfunction "RX2+_A11") (pintype "passive+no_connect"))
    )
    (net (code "46") (name "unconnected-(X5-RX2--PadA10)") (class "Default")
      (node (ref "X5") (pin "A10") (pinfunction "RX2-_A10") (pintype "passive+no_connect"))
    )
    (net (code "47") (name "unconnected-(X5-SBU1-PadA8)") (class "Default")
      (node (ref "X5") (pin "A8") (pinfunction "SBU1_A8") (pintype "passive+no_connect"))
    )
    (net (code "48") (name "unconnected-(X5-SBU2-PadB8)") (class "Default")
      (node (ref "X5") (pin "B8") (pinfunction "SBU2_B8") (pintype "passive+no_connect"))
    )
    (net (code "49") (name "unconnected-(X5-TX1+-PadA2)") (class "Default")
      (node (ref "X5") (pin "A2") (pinfunction "TX1+_A2") (pintype "passive+no_connect"))
    )
    (net (code "50") (name "unconnected-(X5-TX1--PadA3)") (class "Default")
      (node (ref "X5") (pin "A3") (pinfunction "TX1-_A3") (pintype "passive+no_connect"))
    )
    (net (code "51") (name "unconnected-(X5-TX2+-PadB2)") (class "Default")
      (node (ref "X5") (pin "B2") (pinfunction "TX2+_B2") (pintype "passive+no_connect"))
    )
    (net (code "52") (name "unconnected-(X5-TX2--PadB3)") (class "Default")
      (node (ref "X5") (pin "B3") (pinfunction "TX2-_B3") (pintype "passive+no_connect"))
    )
  )
)
